# IMX_Output_Circuit.net
KiCad netlist of a schematic drawn in Altium Designer
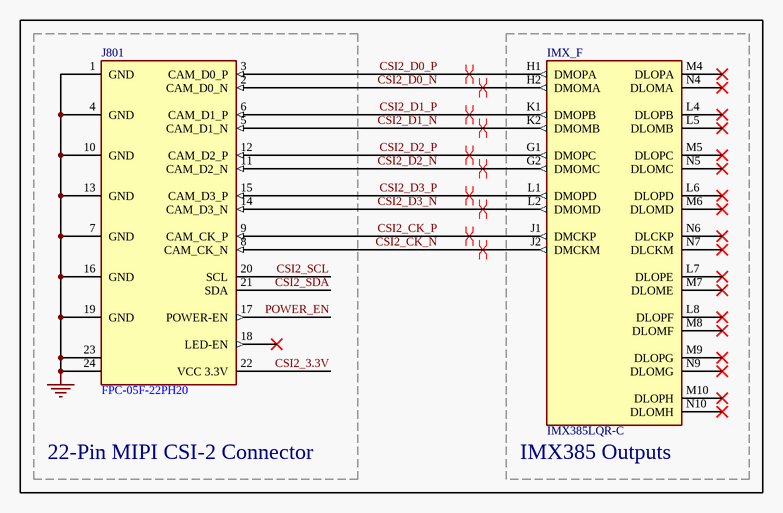
[diagram p0: IMX_Output Circuit.SchDoc]

(export (version "E")
  (design (tool "Eeschema 10.0.6"))
  (components
    (comp (ref "IMX_")
      (value "IMX385LQR-C")
      (footprint "IMX385LQR")
      (libsource (lib "Component Library") (part "IMX385LQR"))
    )
    (comp (ref "J801")
      (value "FPC-05F-22PH20")
      (footprint "FFC Connector")
      (description "SMD,P=0.5mm,Surface Mount, Right Angle, #FPC-05F-22PH20, #C2856804")
      (libsource (lib "Component Library") (part "CSI-2 Connector"))
    )
  )
  (nets
    (net (code "1") (name "/CSI2_3.3V") (class "Default")
      (node (ref "J801") (pin "22") (pinfunction "VCC_3.3V_22") (pintype "passive"))
    )
    (net (code "2") (name "/CSI2_CK_N") (class "Default")
      (node (ref "IMX_") (pin "J2") (pinfunction "DMCKM_J2") (pintype "output"))
      (node (ref "J801") (pin "8") (pinfunction "_CAM_CK_N_8") (pintype "input"))
    )
    (net (code "3") (name "/CSI2_CK_P") (class "Default")
      (node (ref "IMX_") (pin "J1") (pinfunction "DMCKP_J1") (pintype "output"))
      (node (ref "J801") (pin "9") (pinfunction "CAM_CK_P_9") (pintype "input"))
    )
    (net (code "4") (name "/CSI2_D0_N") (class "Default")
      (node (ref "IMX_") (pin "H2") (pinfunction "DMOMA_H2") (pintype "output"))
      (node (ref "J801") (pin "2") (pinfunction "CAM_D0_N_2") (pintype "input"))
    )
    (net (code "5") (name "/CSI2_D0_P") (class "Default")
      (node (ref "IMX_") (pin "H1") (pinfunction "DMOPA_H1") (pintype "output"))
      (node (ref "J801") (pin "3") (pinfunction "CAM_D0_P_3") (pintype "input"))
    )
    (net (code "6") (name "/CSI2_D1_N") (class "Default")
      (node (ref "IMX_") (pin "K2") (pinfunction "DMOMB_K2") (pintype "output"))
      (node (ref "J801") (pin "5") (pinfunction "CAM_D1_N_5") (pintype "input"))
    )
    (net (code "7") (name "/CSI2_D1_P") (class "Default")
      (node (ref "IMX_") (pin "K1") (pinfunction "DMOPB_K1") (pintype "output"))
      (node (ref "J801") (pin "6") (pinfunction "CAM_D1_P_6") (pintype "input"))
    )
    (net (code "8") (name "/CSI2_D2_N") (class "Default")
      (node (ref "IMX_") (pin "G2") (pinfunction "DMOMC_G2") (pintype "output"))
      (node (ref "J801") (pin "11") (pinfunction "CAM_D2_N_11") (pintype "input"))
    )
    (net (code "9") (name "/CSI2_D2_P") (class "Default")
      (node (ref "IMX_") (pin "G1") (pinfunction "DMOPC_G1") (pintype "output"))
      (node (ref "J801") (pin "12") (pinfunction "CAM_D2_P_12") (pintype "input"))
    )
    (net (code "10") (name "/CSI2_D3_N") (class "Default")
      (node (ref "IMX_") (pin "L2") (pinfunction "DMOMD_L2") (pintype "output"))
      (node (ref "J801") (pin "14") (pinfunction "CAM_D3_N_14") (pintype "input"))
    )
    (net (code "11") (name "/CSI2_D3_P") (class "Default")
      (node (ref "IMX_") (pin "L1") (pinfunction "DMOPD_L1") (pintype "output"))
      (node (ref "J801") (pin "15") (pinfunction "CAM_D3_P_15") (pintype "input"))
    )
    (net (code "12") (name "/CSI2_SCL") (class "Default")
      (node (ref "J801") (pin "20") (pinfunction "SCL_20") (pintype "bidirectional"))
    )
    (net (code "13") (name "/CSI2_SDA") (class "Default")
      (node (ref "J801") (pin "21") (pinfunction "SDA_21") (pintype "bidirectional"))
    )
    (net (code "14") (name "/POWER_EN") (class "Default")
      (node (ref "J801") (pin "17") (pinfunction "POWER-EN_17") (pintype "output"))
    )
    (net (code "15") (name "GND") (class "Default")
      (node (ref "J801") (pin "1") (pinfunction "GND_1") (pintype "passive"))
      (node (ref "J801") (pin "10") (pinfunction "GND_10") (pintype "passive"))
      (node (ref "J801") (pin "13") (pinfunction "GND_13") (pintype "passive"))
      (node (ref "J801") (pin "16") (pinfunction "GND_16") (pintype "passive"))
      (node (ref "J801") (pin "19") (pinfunction "GND_19") (pintype "passive"))
      (node (ref "J801") (pin "23") (pintype "passive"))
      (node (ref "J801") (pin "24") (pintype "passive"))
      (node (ref "J801") (pin "4") (pinfunction "GND_4") (pintype "passive"))
      (node (ref "J801") (pin "7") (pinfunction "GND_7") (pintype "passive"))
    )
    (net (code "16") (name "unconnected-(IMX_F-DLCKM-PadN7)") (class "Default")
      (node (ref "IMX_") (pin "N7") (pinfunction "DLCKM_N7") (pintype "passive+no_connect"))
    )
    (net (code "17") (name "unconnected-(IMX_F-DLCKP-PadN6)") (class "Default")
      (node (ref "IMX_") (pin "N6") (pinfunction "DLCKP_N6") (pintype "passive+no_connect"))
    )
    (net (code "18") (name "unconnected-(IMX_F-DLOMA-PadN4)") (class "Default")
      (node (ref "IMX_") (pin "N4") (pinfunction "DLOMA_N4") (pintype "passive+no_connect"))
    )
    (net (code "19") (name "unconnected-(IMX_F-DLOMB-PadL5)") (class "Default")
      (node (ref "IMX_") (pin "L5") (pinfunction "DLOMB_L5") (pintype "passive+no_connect"))
    )
    (net (code "20") (name "unconnected-(IMX_F-DLOMC-PadN5)") (class "Default")
      (node (ref "IMX_") (pin "N5") (pinfunction "DLOMC_N5") (pintype "passive+no_connect"))
    )
    (net (code "21") (name "unconnected-(IMX_F-DLOMD-PadM6)") (class "Default")
      (node (ref "IMX_") (pin "M6") (pinfunction "DLOMD_M6") (pintype "passive+no_connect"))
    )
    (net (code "22") (name "unconnected-(IMX_F-DLOME-PadM7)") (class "Default")
      (node (ref "IMX_") (pin "M7") (pinfunction "DLOME_M7") (pintype "passive+no_connect"))
    )
    (net (code "23") (name "unconnected-(IMX_F-DLOMF-PadM8)") (class "Default")
      (node (ref "IMX_") (pin "M8") (pinfunction "DLOMF_M8") (pintype "passive+no_connect"))
    )
    (net (code "24") (name "unconnected-(IMX_F-DLOMG-PadN9)") (class "Default")
      (node (ref "IMX_") (pin "N9") (pinfunction "DLOMG_N9") (pintype "passive+no_connect"))
    )
    (net (code "25") (name "unconnected-(IMX_F-DLOMH-PadN10)") (class "Default")
      (node (ref "IMX_") (pin "N10") (pinfunction "DLOMH_N10") (pintype "passive+no_connect"))
    )
    (net (code "26") (name "unconnected-(IMX_F-DLOPA-PadM4)") (class "Default")
      (node (ref "IMX_") (pin "M4") (pinfunction "DLOPA_M4") (pintype "passive+no_connect"))
    )
    (net (code "27") (name "unconnected-(IMX_F-DLOPB-PadL4)") (class "Default")
      (node (ref "IMX_") (pin "L4") (pinfunction "DLOPB_L4") (pintype "passive+no_connect"))
    )
    (net (code "28") (name "unconnected-(IMX_F-DLOPC-PadM5)") (class "Default")
      (node (ref "IMX_") (pin "M5") (pinfunction "DLOPC_M5") (pintype "passive+no_connect"))
    )
    (net (code "29") (name "unconnected-(IMX_F-DLOPD-PadL6)") (class "Default")
      (node (ref "IMX_") (pin "L6") (pinfunction "DLOPD_L6") (pintype "passive+no_connect"))
    )
    (net (code "30") (name "unconnected-(IMX_F-DLOPE-PadL7)") (class "Default")
      (node (ref "IMX_") (pin "L7") (pinfunction "DLOPE_L7") (pintype "passive+no_connect"))
    )
    (net (code "31") (name "unconnected-(IMX_F-DLOPF-PadL8)") (class "Default")
      (node (ref "IMX_") (pin "L8") (pinfunction "DLOPF_L8") (pintype "passive+no_connect"))
    )
    (net (code "32") (name "unconnected-(IMX_F-DLOPG-PadM9)") (class "Default")
      (node (ref "IMX_") (pin "M9") (pinfunction "DLOPG_M9") (pintype "passive+no_connect"))
    )
    (net (code "33") (name "unconnected-(IMX_F-DLOPH-PadM10)") (class "Default")
      (node (ref "IMX_") (pin "M10") (pinfunction "DLOPH_M10") (pintype "passive+no_connect"))
    )
    (net (code "34") (name "unconnected-(J801-LED-EN-Pad18)") (class "Default")
      (node (ref "J801") (pin "18") (pinfunction "LED-EN_18") (pintype "output+no_connect"))
    )
  )
)
